# schema_mpb_1_1_Serial.net
KiCad netlist of a schematic drawn in EAGLE
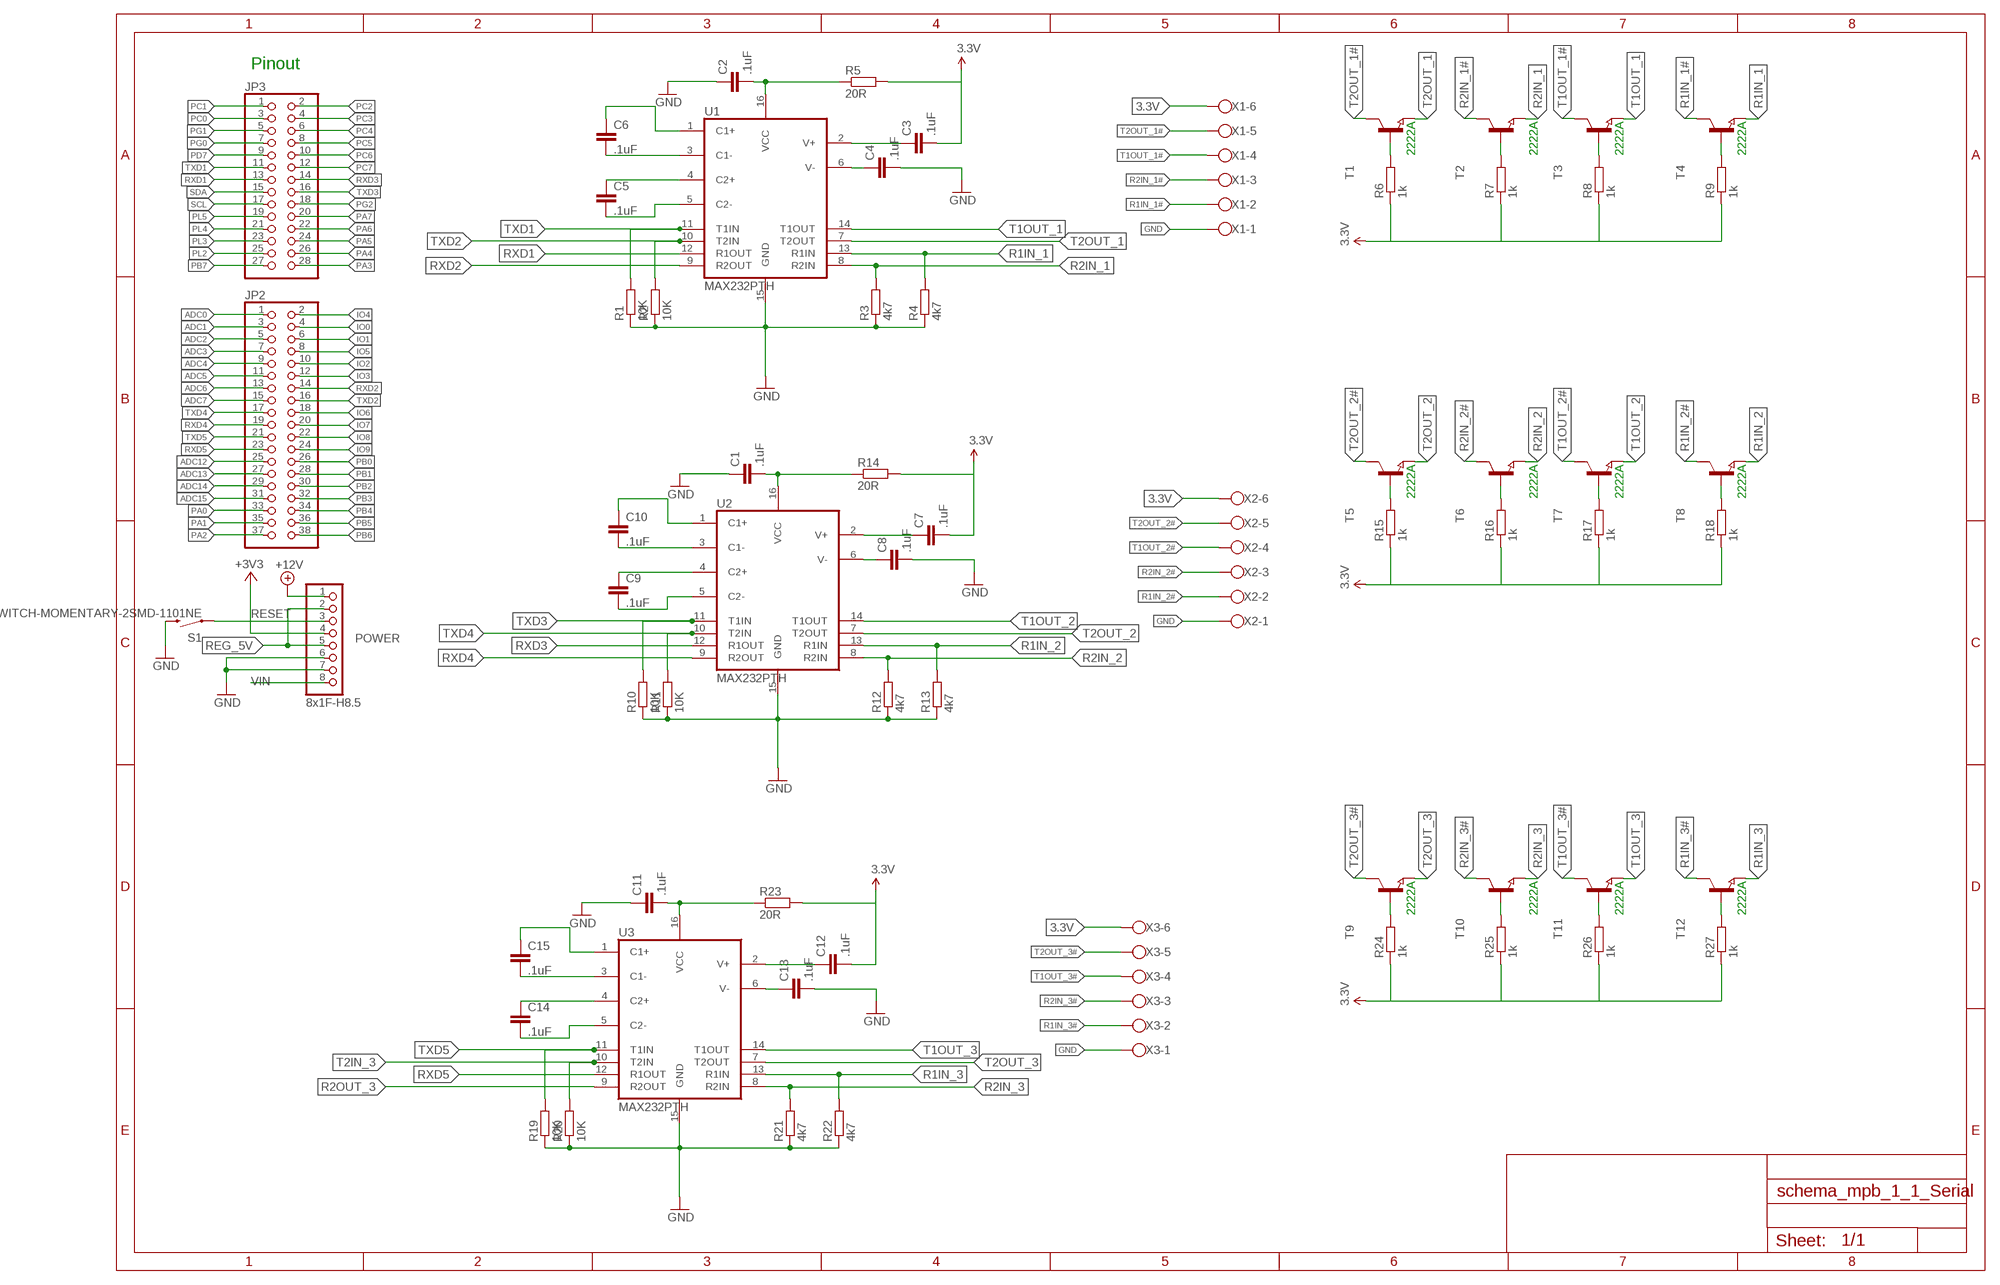
[diagram p0: schematic, sheet 1]

(export (version "E")
  (design (tool "Eeschema 10.0.6"))
  (components
    (comp (ref "C1")
      (value ".1uF")
      (footprint "eagle-import:C0805")
      (libsource (lib "eagle-import") (part "C-EUC0805"))
    )
    (comp (ref "C2")
      (value ".1uF")
      (footprint "eagle-import:C0805")
      (libsource (lib "eagle-import") (part "C-EUC0805"))
    )
    (comp (ref "C3")
      (value ".1uF")
      (footprint "eagle-import:C0805")
      (libsource (lib "eagle-import") (part "C-EUC0805"))
    )
    (comp (ref "C4")
      (value ".1uF")
      (footprint "eagle-import:C0805")
      (libsource (lib "eagle-import") (part "C-EUC0805"))
    )
    (comp (ref "C5")
      (value ".1uF")
      (footprint "eagle-import:C0805")
      (libsource (lib "eagle-import") (part "C-EUC0805"))
    )
    (comp (ref "C6")
      (value ".1uF")
      (footprint "eagle-import:C0805")
      (libsource (lib "eagle-import") (part "C-EUC0805"))
    )
    (comp (ref "C7")
      (value ".1uF")
      (footprint "eagle-import:C0805")
      (libsource (lib "eagle-import") (part "C-EUC0805"))
    )
    (comp (ref "C8")
      (value ".1uF")
      (footprint "eagle-import:C0805")
      (libsource (lib "eagle-import") (part "C-EUC0805"))
    )
    (comp (ref "C9")
      (value ".1uF")
      (footprint "eagle-import:C0805")
      (libsource (lib "eagle-import") (part "C-EUC0805"))
    )
    (comp (ref "C10")
      (value ".1uF")
      (footprint "eagle-import:C0805")
      (libsource (lib "eagle-import") (part "C-EUC0805"))
    )
    (comp (ref "C11")
      (value ".1uF")
      (footprint "eagle-import:C0805")
      (libsource (lib "eagle-import") (part "C-EUC0805"))
    )
    (comp (ref "C12")
      (value ".1uF")
      (footprint "eagle-import:C0805")
      (libsource (lib "eagle-import") (part "C-EUC0805"))
    )
    (comp (ref "C13")
      (value ".1uF")
      (footprint "eagle-import:C0805")
      (libsource (lib "eagle-import") (part "C-EUC0805"))
    )
    (comp (ref "C14")
      (value ".1uF")
      (footprint "eagle-import:C0805")
      (libsource (lib "eagle-import") (part "C-EUC0805"))
    )
    (comp (ref "C15")
      (value ".1uF")
      (footprint "eagle-import:C0805")
      (libsource (lib "eagle-import") (part "C-EUC0805"))
    )
    (comp (ref "JP2")
      (value "PINHD-2X19")
      (footprint "eagle-import:2X19")
      (libsource (lib "eagle-import") (part "PINHD-2X19"))
    )
    (comp (ref "JP3")
      (value "PINHD-2X14")
      (footprint "eagle-import:2X14")
      (libsource (lib "eagle-import") (part "PINHD-2X14"))
    )
    (comp (ref "POWER")
      (value "8x1F-H8.5")
      (footprint "eagle-import:1X08")
      (libsource (lib "eagle-import") (part "PINHD-1X8"))
    )
    (comp (ref "R1")
      (value "10K")
      (footprint "eagle-import:R0805")
      (libsource (lib "eagle-import") (part "R-EU_R0805"))
    )
    (comp (ref "R2")
      (value "10K")
      (footprint "eagle-import:R0805")
      (libsource (lib "eagle-import") (part "R-EU_R0805"))
    )
    (comp (ref "R3")
      (value "4k7")
      (footprint "eagle-import:R0805")
      (libsource (lib "eagle-import") (part "R-EU_R0805"))
    )
    (comp (ref "R4")
      (value "4k7")
      (footprint "eagle-import:R0805")
      (libsource (lib "eagle-import") (part "R-EU_R0805"))
    )
    (comp (ref "R5")
      (value "20R")
      (footprint "eagle-import:R0805")
      (libsource (lib "eagle-import") (part "R-EU_R0805"))
    )
    (comp (ref "R6")
      (value "1k")
      (footprint "eagle-import:R0805")
      (libsource (lib "eagle-import") (part "R-EU_R0805"))
    )
    (comp (ref "R7")
      (value "1k")
      (footprint "eagle-import:R0805")
      (libsource (lib "eagle-import") (part "R-EU_R0805"))
    )
    (comp (ref "R8")
      (value "1k")
      (footprint "eagle-import:R0805")
      (libsource (lib "eagle-import") (part "R-EU_R0805"))
    )
    (comp (ref "R9")
      (value "1k")
      (footprint "eagle-import:R0805")
      (libsource (lib "eagle-import") (part "R-EU_R0805"))
    )
    (comp (ref "R10")
      (value "10K")
      (footprint "eagle-import:R0805")
      (libsource (lib "eagle-import") (part "R-EU_R0805"))
    )
    (comp (ref "R11")
      (value "10K")
      (footprint "eagle-import:R0805")
      (libsource (lib "eagle-import") (part "R-EU_R0805"))
    )
    (comp (ref "R12")
      (value "4k7")
      (footprint "eagle-import:R0805")
      (libsource (lib "eagle-import") (part "R-EU_R0805"))
    )
    (comp (ref "R13")
      (value "4k7")
      (footprint "eagle-import:R0805")
      (libsource (lib "eagle-import") (part "R-EU_R0805"))
    )
    (comp (ref "R14")
      (value "20R")
      (footprint "eagle-import:R0805")
      (libsource (lib "eagle-import") (part "R-EU_R0805"))
    )
    (comp (ref "R15")
      (value "1k")
      (footprint "eagle-import:R0805")
      (libsource (lib "eagle-import") (part "R-EU_R0805"))
    )
    (comp (ref "R16")
      (value "1k")
      (footprint "eagle-import:R0805")
      (libsource (lib "eagle-import") (part "R-EU_R0805"))
    )
    (comp (ref "R17")
      (value "1k")
      (footprint "eagle-import:R0805")
      (libsource (lib "eagle-import") (part "R-EU_R0805"))
    )
    (comp (ref "R18")
      (value "1k")
      (footprint "eagle-import:R0805")
      (libsource (lib "eagle-import") (part "R-EU_R0805"))
    )
    (comp (ref "R19")
      (value "10K")
      (footprint "eagle-import:R0805")
      (libsource (lib "eagle-import") (part "R-EU_R0805"))
    )
    (comp (ref "R20")
      (value "10K")
      (footprint "eagle-import:R0805")
      (libsource (lib "eagle-import") (part "R-EU_R0805"))
    )
    (comp (ref "R21")
      (value "4k7")
      (footprint "eagle-import:R0805")
      (libsource (lib "eagle-import") (part "R-EU_R0805"))
    )
    (comp (ref "R22")
      (value "4k7")
      (footprint "eagle-import:R0805")
      (libsource (lib "eagle-import") (part "R-EU_R0805"))
    )
    (comp (ref "R23")
      (value "20R")
      (footprint "eagle-import:R0805")
      (libsource (lib "eagle-import") (part "R-EU_R0805"))
    )
    (comp (ref "R24")
      (value "1k")
      (footprint "eagle-import:R0805")
      (libsource (lib "eagle-import") (part "R-EU_R0805"))
    )
    (comp (ref "R25")
      (value "1k")
      (footprint "eagle-import:R0805")
      (libsource (lib "eagle-import") (part "R-EU_R0805"))
    )
    (comp (ref "R26")
      (value "1k")
      (footprint "eagle-import:R0805")
      (libsource (lib "eagle-import") (part "R-EU_R0805"))
    )
    (comp (ref "R27")
      (value "1k")
      (footprint "eagle-import:R0805")
      (libsource (lib "eagle-import") (part "R-EU_R0805"))
    )
    (comp (ref "S1")
      (value "SWITCH-MOMENTARY-2SMD-1101NE")
      (footprint "eagle-import:TACTILE-SWITCH-1101NE")
      (libsource (lib "eagle-import") (part "SWITCH-MOMENTARY-2SMD-1101NE"))
    )
    (comp (ref "T1")
      (value "NPN-TRANSISTOR_SOT23")
      (footprint "eagle-import:SOT23")
      (libsource (lib "eagle-import") (part "NPN-TRANSISTOR_SOT23"))
    )
    (comp (ref "T2")
      (value "NPN-TRANSISTOR_SOT23")
      (footprint "eagle-import:SOT23")
      (libsource (lib "eagle-import") (part "NPN-TRANSISTOR_SOT23"))
    )
    (comp (ref "T3")
      (value "NPN-TRANSISTOR_SOT23")
      (footprint "eagle-import:SOT23")
      (libsource (lib "eagle-import") (part "NPN-TRANSISTOR_SOT23"))
    )
    (comp (ref "T4")
      (value "NPN-TRANSISTOR_SOT23")
      (footprint "eagle-import:SOT23")
      (libsource (lib "eagle-import") (part "NPN-TRANSISTOR_SOT23"))
    )
    (comp (ref "T5")
      (value "NPN-TRANSISTOR_SOT23")
      (footprint "eagle-import:SOT23")
      (libsource (lib "eagle-import") (part "NPN-TRANSISTOR_SOT23"))
    )
    (comp (ref "T6")
      (value "NPN-TRANSISTOR_SOT23")
      (footprint "eagle-import:SOT23")
      (libsource (lib "eagle-import") (part "NPN-TRANSISTOR_SOT23"))
    )
    (comp (ref "T7")
      (value "NPN-TRANSISTOR_SOT23")
      (footprint "eagle-import:SOT23")
      (libsource (lib "eagle-import") (part "NPN-TRANSISTOR_SOT23"))
    )
    (comp (ref "T8")
      (value "NPN-TRANSISTOR_SOT23")
      (footprint "eagle-import:SOT23")
      (libsource (lib "eagle-import") (part "NPN-TRANSISTOR_SOT23"))
    )
    (comp (ref "T9")
      (value "NPN-TRANSISTOR_SOT23")
      (footprint "eagle-import:SOT23")
      (libsource (lib "eagle-import") (part "NPN-TRANSISTOR_SOT23"))
    )
    (comp (ref "T10")
      (value "NPN-TRANSISTOR_SOT23")
      (footprint "eagle-import:SOT23")
      (libsource (lib "eagle-import") (part "NPN-TRANSISTOR_SOT23"))
    )
    (comp (ref "T11")
      (value "NPN-TRANSISTOR_SOT23")
      (footprint "eagle-import:SOT23")
      (libsource (lib "eagle-import") (part "NPN-TRANSISTOR_SOT23"))
    )
    (comp (ref "T12")
      (value "NPN-TRANSISTOR_SOT23")
      (footprint "eagle-import:SOT23")
      (libsource (lib "eagle-import") (part "NPN-TRANSISTOR_SOT23"))
    )
    (comp (ref "U1")
      (value "MAX232PTH")
      (footprint "eagle-import:DIL16")
      (libsource (lib "eagle-import") (part "MAX232PTH"))
    )
    (comp (ref "U2")
      (value "MAX232PTH")
      (footprint "eagle-import:DIL16")
      (libsource (lib "eagle-import") (part "MAX232PTH"))
    )
    (comp (ref "U3")
      (value "MAX232PTH")
      (footprint "eagle-import:DIL16")
      (libsource (lib "eagle-import") (part "MAX232PTH"))
    )
    (comp (ref "X1")
      (value "W237-6")
      (footprint "eagle-import:W237-6")
      (libsource (lib "eagle-import") (part "W237-6"))
    )
    (comp (ref "X2")
      (value "W237-6")
      (footprint "eagle-import:W237-6")
      (libsource (lib "eagle-import") (part "W237-6"))
    )
    (comp (ref "X3")
      (value "W237-6")
      (footprint "eagle-import:W237-6")
      (libsource (lib "eagle-import") (part "W237-6"))
    )
  )
  (nets
    (net (code "1") (name "+12V") (class "Default")
      (node (ref "POWER") (pin "1") (pinfunction "1_1") (pintype "passive"))
    )
    (net (code "2") (name "/RESET") (class "Default")
      (node (ref "POWER") (pin "3") (pinfunction "3_3") (pintype "passive"))
      (node (ref "S1") (pin "1") (pinfunction "1_1") (pintype "passive"))
    )
    (net (code "3") (name "/VIN") (class "Default")
      (node (ref "POWER") (pin "8") (pinfunction "8_8") (pintype "passive"))
    )
    (net (code "4") (name "3.3V") (class "Default")
      (node (ref "C12") (pin "2") (pinfunction "2_2") (pintype "passive"))
      (node (ref "C3") (pin "2") (pinfunction "2_2") (pintype "passive"))
      (node (ref "C7") (pin "2") (pinfunction "2_2") (pintype "passive"))
      (node (ref "POWER") (pin "4") (pinfunction "4_4") (pintype "passive"))
      (node (ref "R14") (pin "2") (pinfunction "2_2") (pintype "passive"))
      (node (ref "R15") (pin "1") (pinfunction "1_1") (pintype "passive"))
      (node (ref "R16") (pin "1") (pinfunction "1_1") (pintype "passive"))
      (node (ref "R17") (pin "1") (pinfunction "1_1") (pintype "passive"))
      (node (ref "R18") (pin "1") (pinfunction "1_1") (pintype "passive"))
      (node (ref "R23") (pin "2") (pinfunction "2_2") (pintype "passive"))
      (node (ref "R24") (pin "1") (pinfunction "1_1") (pintype "passive"))
      (node (ref "R25") (pin "1") (pinfunction "1_1") (pintype "passive"))
      (node (ref "R26") (pin "1") (pinfunction "1_1") (pintype "passive"))
      (node (ref "R27") (pin "1") (pinfunction "1_1") (pintype "passive"))
      (node (ref "R5") (pin "2") (pinfunction "2_2") (pintype "passive"))
      (node (ref "R6") (pin "1") (pinfunction "1_1") (pintype "passive"))
      (node (ref "R7") (pin "1") (pinfunction "1_1") (pintype "passive"))
      (node (ref "R8") (pin "1") (pinfunction "1_1") (pintype "passive"))
      (node (ref "R9") (pin "1") (pinfunction "1_1") (pintype "passive"))
      (node (ref "X1") (pin "6") (pinfunction "KL_6") (pintype "passive"))
      (node (ref "X2") (pin "6") (pinfunction "KL_6") (pintype "passive"))
      (node (ref "X3") (pin "6") (pinfunction "KL_6") (pintype "passive"))
    )
    (net (code "5") (name "ADC0") (class "Default")
      (node (ref "JP2") (pin "1") (pinfunction "1_1") (pintype "passive"))
    )
    (net (code "6") (name "ADC1") (class "Default")
      (node (ref "JP2") (pin "3") (pinfunction "3_3") (pintype "passive"))
    )
    (net (code "7") (name "ADC2") (class "Default")
      (node (ref "JP2") (pin "5") (pinfunction "5_5") (pintype "passive"))
    )
    (net (code "8") (name "ADC3") (class "Default")
      (node (ref "JP2") (pin "7") (pinfunction "7_7") (pintype "passive"))
    )
    (net (code "9") (name "ADC4") (class "Default")
      (node (ref "JP2") (pin "9") (pinfunction "9_9") (pintype "passive"))
    )
    (net (code "10") (name "ADC5") (class "Default")
      (node (ref "JP2") (pin "11") (pinfunction "11_11") (pintype "passive"))
    )
    (net (code "11") (name "ADC6") (class "Default")
      (node (ref "JP2") (pin "13") (pinfunction "13_13") (pintype "passive"))
    )
    (net (code "12") (name "ADC7") (class "Default")
      (node (ref "JP2") (pin "15") (pinfunction "15_15") (pintype "passive"))
    )
    (net (code "13") (name "ADC12") (class "Default")
      (node (ref "JP2") (pin "25") (pinfunction "25_25") (pintype "passive"))
    )
    (net (code "14") (name "ADC13") (class "Default")
      (node (ref "JP2") (pin "27") (pinfunction "27_27") (pintype "passive"))
    )
    (net (code "15") (name "ADC14") (class "Default")
      (node (ref "JP2") (pin "29") (pinfunction "29_29") (pintype "passive"))
    )
    (net (code "16") (name "ADC15") (class "Default")
      (node (ref "JP2") (pin "31") (pinfunction "31_31") (pintype "passive"))
    )
    (net (code "17") (name "GND") (class "Default")
      (node (ref "C1") (pin "1") (pinfunction "1_1") (pintype "passive"))
      (node (ref "C11") (pin "1") (pinfunction "1_1") (pintype "passive"))
      (node (ref "C13") (pin "2") (pinfunction "2_2") (pintype "passive"))
      (node (ref "C2") (pin "1") (pinfunction "1_1") (pintype "passive"))
      (node (ref "C4") (pin "2") (pinfunction "2_2") (pintype "passive"))
      (node (ref "C8") (pin "2") (pinfunction "2_2") (pintype "passive"))
      (node (ref "POWER") (pin "6") (pinfunction "6_6") (pintype "passive"))
      (node (ref "POWER") (pin "7") (pinfunction "7_7") (pintype "passive"))
      (node (ref "R1") (pin "1") (pinfunction "1_1") (pintype "passive"))
      (node (ref "R10") (pin "1") (pinfunction "1_1") (pintype "passive"))
      (node (ref "R11") (pin "1") (pinfunction "1_1") (pintype "passive"))
      (node (ref "R12") (pin "1") (pinfunction "1_1") (pintype "passive"))
      (node (ref "R13") (pin "1") (pinfunction "1_1") (pintype "passive"))
      (node (ref "R19") (pin "1") (pinfunction "1_1") (pintype "passive"))
      (node (ref "R2") (pin "1") (pinfunction "1_1") (pintype "passive"))
      (node (ref "R20") (pin "1") (pinfunction "1_1") (pintype "passive"))
      (node (ref "R21") (pin "1") (pinfunction "1_1") (pintype "passive"))
      (node (ref "R22") (pin "1") (pinfunction "1_1") (pintype "passive"))
      (node (ref "R3") (pin "1") (pinfunction "1_1") (pintype "passive"))
      (node (ref "R4") (pin "1") (pinfunction "1_1") (pintype "passive"))
      (node (ref "S1") (pin "2") (pinfunction "2_2") (pintype "passive"))
      (node (ref "U1") (pin "15") (pinfunction "GND_15") (pintype "bidirectional"))
      (node (ref "U2") (pin "15") (pinfunction "GND_15") (pintype "bidirectional"))
      (node (ref "U3") (pin "15") (pinfunction "GND_15") (pintype "bidirectional"))
      (node (ref "X1") (pin "1") (pinfunction "KL_1") (pintype "passive"))
      (node (ref "X2") (pin "1") (pinfunction "KL_1") (pintype "passive"))
      (node (ref "X3") (pin "1") (pinfunction "KL_1") (pintype "passive"))
    )
    (net (code "18") (name "IO0") (class "Default")
      (node (ref "JP2") (pin "4") (pinfunction "4_4") (pintype "passive"))
    )
    (net (code "19") (name "IO1") (class "Default")
      (node (ref "JP2") (pin "6") (pinfunction "6_6") (pintype "passive"))
    )
    (net (code "20") (name "IO2") (class "Default")
      (node (ref "JP2") (pin "10") (pinfunction "10_10") (pintype "passive"))
    )
    (net (code "21") (name "IO3") (class "Default")
      (node (ref "JP2") (pin "12") (pinfunction "12_12") (pintype "passive"))
    )
    (net (code "22") (name "IO4") (class "Default")
      (node (ref "JP2") (pin "2") (pinfunction "2_2") (pintype "passive"))
    )
    (net (code "23") (name "IO5") (class "Default")
      (node (ref "JP2") (pin "8") (pinfunction "8_8") (pintype "passive"))
    )
    (net (code "24") (name "IO6") (class "Default")
      (node (ref "JP2") (pin "18") (pinfunction "18_18") (pintype "passive"))
    )
    (net (code "25") (name "IO7") (class "Default")
      (node (ref "JP2") (pin "20") (pinfunction "20_20") (pintype "passive"))
    )
    (net (code "26") (name "IO8") (class "Default")
      (node (ref "JP2") (pin "22") (pinfunction "22_22") (pintype "passive"))
    )
    (net (code "27") (name "IO9") (class "Default")
      (node (ref "JP2") (pin "24") (pinfunction "24_24") (pintype "passive"))
    )
    (net (code "28") (name "Net-(T1-B)") (class "Default")
      (node (ref "R6") (pin "2") (pinfunction "2_2") (pintype "passive"))
      (node (ref "T1") (pin "1") (pinfunction "B_1") (pintype "passive"))
    )
    (net (code "29") (name "Net-(T2-B)") (class "Default")
      (node (ref "R7") (pin "2") (pinfunction "2_2") (pintype "passive"))
      (node (ref "T2") (pin "1") (pinfunction "B_1") (pintype "passive"))
    )
    (net (code "30") (name "Net-(T3-B)") (class "Default")
      (node (ref "R8") (pin "2") (pinfunction "2_2") (pintype "passive"))
      (node (ref "T3") (pin "1") (pinfunction "B_1") (pintype "passive"))
    )
    (net (code "31") (name "Net-(T4-B)") (class "Default")
      (node (ref "R9") (pin "2") (pinfunction "2_2") (pintype "passive"))
      (node (ref "T4") (pin "1") (pinfunction "B_1") (pintype "passive"))
    )
    (net (code "32") (name "Net-(T5-B)") (class "Default")
      (node (ref "R15") (pin "2") (pinfunction "2_2") (pintype "passive"))
      (node (ref "T5") (pin "1") (pinfunction "B_1") (pintype "passive"))
    )
    (net (code "33") (name "Net-(T6-B)") (class "Default")
      (node (ref "R16") (pin "2") (pinfunction "2_2") (pintype "passive"))
      (node (ref "T6") (pin "1") (pinfunction "B_1") (pintype "passive"))
    )
    (net (code "34") (name "Net-(T7-B)") (class "Default")
      (node (ref "R17") (pin "2") (pinfunction "2_2") (pintype "passive"))
      (node (ref "T7") (pin "1") (pinfunction "B_1") (pintype "passive"))
    )
    (net (code "35") (name "Net-(T8-B)") (class "Default")
      (node (ref "R18") (pin "2") (pinfunction "2_2") (pintype "passive"))
      (node (ref "T8") (pin "1") (pinfunction "B_1") (pintype "passive"))
    )
    (net (code "36") (name "Net-(T9-B)") (class "Default")
      (node (ref "R24") (pin "2") (pinfunction "2_2") (pintype "passive"))
      (node (ref "T9") (pin "1") (pinfunction "B_1") (pintype "passive"))
    )
    (net (code "37") (name "Net-(T10-B)") (class "Default")
      (node (ref "R25") (pin "2") (pinfunction "2_2") (pintype "passive"))
      (node (ref "T10") (pin "1") (pinfunction "B_1") (pintype "passive"))
    )
    (net (code "38") (name "Net-(T11-B)") (class "Default")
      (node (ref "R26") (pin "2") (pinfunction "2_2") (pintype "passive"))
      (node (ref "T11") (pin "1") (pinfunction "B_1") (pintype "passive"))
    )
    (net (code "39") (name "Net-(T12-B)") (class "Default")
      (node (ref "R27") (pin "2") (pinfunction "2_2") (pintype "passive"))
      (node (ref "T12") (pin "1") (pinfunction "B_1") (pintype "passive"))
    )
    (net (code "40") (name "Net-(U1-C1+)") (class "Default")
      (node (ref "C6") (pin "1") (pinfunction "1_1") (pintype "passive"))
      (node (ref "U1") (pin "1") (pinfunction "C1+_1") (pintype "bidirectional"))
    )
    (net (code "41") (name "Net-(U1-C1-)") (class "Default")
      (node (ref "C6") (pin "2") (pinfunction "2_2") (pintype "passive"))
      (node (ref "U1") (pin "3") (pinfunction "C1-_3") (pintype "bidirectional"))
    )
    (net (code "42") (name "Net-(U1-C2+)") (class "Default")
      (node (ref "C5") (pin "1") (pinfunction "1_1") (pintype "passive"))
      (node (ref "U1") (pin "4") (pinfunction "C2+_4") (pintype "bidirectional"))
    )
    (net (code "43") (name "Net-(U1-C2-)") (class "Default")
      (node (ref "C5") (pin "2") (pinfunction "2_2") (pintype "passive"))
      (node (ref "U1") (pin "5") (pinfunction "C2-_5") (pintype "bidirectional"))
    )
    (net (code "44") (name "Net-(U1-V+)") (class "Default")
      (node (ref "C3") (pin "1") (pinfunction "1_1") (pintype "passive"))
      (node (ref "U1") (pin "2") (pinfunction "V+_2") (pintype "bidirectional"))
    )
    (net (code "45") (name "Net-(U1-V-)") (class "Default")
      (node (ref "C4") (pin "1") (pinfunction "1_1") (pintype "passive"))
      (node (ref "U1") (pin "6") (pinfunction "V-_6") (pintype "bidirectional"))
    )
    (net (code "46") (name "Net-(U1-VCC)") (class "Default")
      (node (ref "C2") (pin "2") (pinfunction "2_2") (pintype "passive"))
      (node (ref "R5") (pin "1") (pinfunction "1_1") (pintype "passive"))
      (node (ref "U1") (pin "16") (pinfunction "VCC_16") (pintype "bidirectional"))
    )
    (net (code "47") (name "Net-(U2-C1+)") (class "Default")
      (node (ref "C10") (pin "1") (pinfunction "1_1") (pintype "passive"))
      (node (ref "U2") (pin "1") (pinfunction "C1+_1") (pintype "bidirectional"))
    )
    (net (code "48") (name "Net-(U2-C1-)") (class "Default")
      (node (ref "C10") (pin "2") (pinfunction "2_2") (pintype "passive"))
      (node (ref "U2") (pin "3") (pinfunction "C1-_3") (pintype "bidirectional"))
    )
    (net (code "49") (name "Net-(U2-C2+)") (class "Default")
      (node (ref "C9") (pin "1") (pinfunction "1_1") (pintype "passive"))
      (node (ref "U2") (pin "4") (pinfunction "C2+_4") (pintype "bidirectional"))
    )
    (net (code "50") (name "Net-(U2-C2-)") (class "Default")
      (node (ref "C9") (pin "2") (pinfunction "2_2") (pintype "passive"))
      (node (ref "U2") (pin "5") (pinfunction "C2-_5") (pintype "bidirectional"))
    )
    (net (code "51") (name "Net-(U2-V+)") (class "Default")
      (node (ref "C7") (pin "1") (pinfunction "1_1") (pintype "passive"))
      (node (ref "U2") (pin "2") (pinfunction "V+_2") (pintype "bidirectional"))
    )
    (net (code "52") (name "Net-(U2-V-)") (class "Default")
      (node (ref "C8") (pin "1") (pinfunction "1_1") (pintype "passive"))
      (node (ref "U2") (pin "6") (pinfunction "V-_6") (pintype "bidirectional"))
    )
    (net (code "53") (name "Net-(U2-VCC)") (class "Default")
      (node (ref "C1") (pin "2") (pinfunction "2_2") (pintype "passive"))
      (node (ref "R14") (pin "1") (pinfunction "1_1") (pintype "passive"))
      (node (ref "U2") (pin "16") (pinfunction "VCC_16") (pintype "bidirectional"))
    )
    (net (code "54") (name "Net-(U3-C1+)") (class "Default")
      (node (ref "C15") (pin "1") (pinfunction "1_1") (pintype "passive"))
      (node (ref "U3") (pin "1") (pinfunction "C1+_1") (pintype "bidirectional"))
    )
    (net (code "55") (name "Net-(U3-C1-)") (class "Default")
      (node (ref "C15") (pin "2") (pinfunction "2_2") (pintype "passive"))
      (node (ref "U3") (pin "3") (pinfunction "C1-_3") (pintype "bidirectional"))
    )
    (net (code "56") (name "Net-(U3-C2+)") (class "Default")
      (node (ref "C14") (pin "1") (pinfunction "1_1") (pintype "passive"))
      (node (ref "U3") (pin "4") (pinfunction "C2+_4") (pintype "bidirectional"))
    )
    (net (code "57") (name "Net-(U3-C2-)") (class "Default")
      (node (ref "C14") (pin "2") (pinfunction "2_2") (pintype "passive"))
      (node (ref "U3") (pin "5") (pinfunction "C2-_5") (pintype "bidirectional"))
    )
    (net (code "58") (name "Net-(U3-V+)") (class "Default")
      (node (ref "C12") (pin "1") (pinfunction "1_1") (pintype "passive"))
      (node (ref "U3") (pin "2") (pinfunction "V+_2") (pintype "bidirectional"))
    )
    (net (code "59") (name "Net-(U3-V-)") (class "Default")
      (node (ref "C13") (pin "1") (pinfunction "1_1") (pintype "passive"))
      (node (ref "U3") (pin "6") (pinfunction "V-_6") (pintype "bidirectional"))
    )
    (net (code "60") (name "Net-(U3-VCC)") (class "Default")
      (node (ref "C11") (pin "2") (pinfunction "2_2") (pintype "passive"))
      (node (ref "R23") (pin "1") (pinfunction "1_1") (pintype "passive"))
      (node (ref "U3") (pin "16") (pinfunction "VCC_16") (pintype "bidirectional"))
    )
    (net (code "61") (name "PA0") (class "Default")
      (node (ref "JP2") (pin "33") (pinfunction "33_33") (pintype "passive"))
    )
    (net (code "62") (name "PA1") (class "Default")
      (node (ref "JP2") (pin "35") (pinfunction "35_35") (pintype "passive"))
    )
    (net (code "63") (name "PA2") (class "Default")
      (node (ref "JP2") (pin "37") (pinfunction "37_37") (pintype "passive"))
    )
    (net (code "64") (name "PA3") (class "Default")
      (node (ref "JP3") (pin "28") (pinfunction "28_28") (pintype "passive"))
    )
    (net (code "65") (name "PA4") (class "Default")
      (node (ref "JP3") (pin "26") (pinfunction "26_26") (pintype "passive"))
    )
    (net (code "66") (name "PA5") (class "Default")
      (node (ref "JP3") (pin "24") (pinfunction "24_24") (pintype "passive"))
    )
    (net (code "67") (name "PA6") (class "Default")
      (node (ref "JP3") (pin "22") (pinfunction "22_22") (pintype "passive"))
    )
    (net (code "68") (name "PA7") (class "Default")
      (node (ref "JP3") (pin "20") (pinfunction "20_20") (pintype "passive"))
    )
    (net (code "69") (name "PB0") (class "Default")
      (node (ref "JP2") (pin "26") (pinfunction "26_26") (pintype "passive"))
    )
    (net (code "70") (name "PB1") (class "Default")
      (node (ref "JP2") (pin "28") (pinfunction "28_28") (pintype "passive"))
    )
    (net (code "71") (name "PB2") (class "Default")
      (node (ref "JP2") (pin "30") (pinfunction "30_30") (pintype "passive"))
    )
    (net (code "72") (name "PB3") (class "Default")
      (node (ref "JP2") (pin "32") (pinfunction "32_32") (pintype "passive"))
    )
    (net (code "73") (name "PB4") (class "Default")
      (node (ref "JP2") (pin "34") (pinfunction "34_34") (pintype "passive"))
    )
    (net (code "74") (name "PB5") (class "Default")
      (node (ref "JP2") (pin "36") (pinfunction "36_36") (pintype "passive"))
    )
    (net (code "75") (name "PB6") (class "Default")
      (node (ref "JP2") (pin "38") (pinfunction "38_38") (pintype "passive"))
    )
    (net (code "76") (name "PB7") (class "Default")
      (node (ref "JP3") (pin "27") (pinfunction "27_27") (pintype "passive"))
    )
    (net (code "77") (name "PC0") (class "Default")
      (node (ref "JP3") (pin "3") (pinfunction "3_3") (pintype "passive"))
    )
    (net (code "78") (name "PC1") (class "Default")
      (node (ref "JP3") (pin "1") (pinfunction "1_1") (pintype "passive"))
    )
    (net (code "79") (name "PC2") (class "Default")
      (node (ref "JP3") (pin "2") (pinfunction "2_2") (pintype "passive"))
    )
    (net (code "80") (name "PC3") (class "Default")
      (node (ref "JP3") (pin "4") (pinfunction "4_4") (pintype "passive"))
    )
    (net (code "81") (name "PC4") (class "Default")
      (node (ref "JP3") (pin "6") (pinfunction "6_6") (pintype "passive"))
    )
    (net (code "82") (name "PC5") (class "Default")
      (node (ref "JP3") (pin "8") (pinfunction "8_8") (pintype "passive"))
    )
    (net (code "83") (name "PC6") (class "Default")
      (node (ref "JP3") (pin "10") (pinfunction "10_10") (pintype "passive"))
    )
    (net (code "84") (name "PC7") (class "Default")
      (node (ref "JP3") (pin "12") (pinfunction "12_12") (pintype "passive"))
    )
    (net (code "85") (name "PD7") (class "Default")
      (node (ref "JP3") (pin "9") (pinfunction "9_9") (pintype "passive"))
    )
    (net (code "86") (name "PG0") (class "Default")
      (node (ref "JP3") (pin "7") (pinfunction "7_7") (pintype "passive"))
    )
    (net (code "87") (name "PG1") (class "Default")
      (node (ref "JP3") (pin "5") (pinfunction "5_5") (pintype "passive"))
    )
    (net (code "88") (name "PG2") (class "Default")
      (node (ref "JP3") (pin "18") (pinfunction "18_18") (pintype "passive"))
    )
    (net (code "89") (name "PL2") (class "Default")
      (node (ref "JP3") (pin "25") (pinfunction "25_25") (pintype "passive"))
    )
    (net (code "90") (name "PL3") (class "Default")
      (node (ref "JP3") (pin "23") (pinfunction "23_23") (pintype "passive"))
    )
    (net (code "91") (name "PL4") (class "Default")
      (node (ref "JP3") (pin "21") (pinfunction "21_21") (pintype "passive"))
    )
    (net (code "92") (name "PL5") (class "Default")
      (node (ref "JP3") (pin "19") (pinfunction "19_19") (pintype "passive"))
    )
    (net (code "93") (name "R1IN_1") (class "Default")
      (node (ref "R4") (pin "2") (pinfunction "2_2") (pintype "passive"))
      (node (ref "T4") (pin "2") (pinfunction "E_2") (pintype "passive"))
      (node (ref "U1") (pin "13") (pinfunction "R1IN_13") (pintype "input"))
    )
    (net (code "94") (name "R1IN_1#") (class "Default")
      (node (ref "T4") (pin "3") (pinfunction "C_3") (pintype "passive"))
      (node (ref "X1") (pin "2") (pinfunction "KL_2") (pintype "passive"))
    )
    (net (code "95") (name "R1IN_2") (class "Default")
      (node (ref "R13") (pin "2") (pinfunction "2_2") (pintype "passive"))
      (node (ref "T8") (pin "2") (pinfunction "E_2") (pintype "passive"))
      (node (ref "U2") (pin "13") (pinfunction "R1IN_13") (pintype "input"))
    )
    (net (code "96") (name "R1IN_2#") (class "Default")
      (node (ref "T8") (pin "3") (pinfunction "C_3") (pintype "passive"))
      (node (ref "X2") (pin "2") (pinfunction "KL_2") (pintype "passive"))
    )
    (net (code "97") (name "R1IN_3") (class "Default")
      (node (ref "R22") (pin "2") (pinfunction "2_2") (pintype "passive"))
      (node (ref "T12") (pin "2") (pinfunction "E_2") (pintype "passive"))
      (node (ref "U3") (pin "13") (pinfunction "R1IN_13") (pintype "input"))
    )
    (net (code "98") (name "R1IN_3#") (class "Default")
      (node (ref "T12") (pin "3") (pinfunction "C_3") (pintype "passive"))
      (node (ref "X3") (pin "2") (pinfunction "KL_2") (pintype "passive"))
    )
    (net (code "99") (name "R2IN_1") (class "Default")
      (node (ref "R3") (pin "2") (pinfunction "2_2") (pintype "passive"))
      (node (ref "T2") (pin "2") (pinfunction "E_2") (pintype "passive"))
      (node (ref "U1") (pin "8") (pinfunction "R2IN_8") (pintype "input"))
    )
    (net (code "100") (name "R2IN_1#") (class "Default")
      (node (ref "T2") (pin "3") (pinfunction "C_3") (pintype "passive"))
      (node (ref "X1") (pin "3") (pinfunction "KL_3") (pintype "passive"))
    )
    (net (code "101") (name "R2IN_2") (class "Default")
      (node (ref "R12") (pin "2") (pinfunction "2_2") (pintype "passive"))
      (node (ref "T6") (pin "2") (pinfunction "E_2") (pintype "passive"))
      (node (ref "U2") (pin "8") (pinfunction "R2IN_8") (pintype "input"))
    )
    (net (code "102") (name "R2IN_2#") (class "Default")
      (node (ref "T6") (pin "3") (pinfunction "C_3") (pintype "passive"))
      (node (ref "X2") (pin "3") (pinfunction "KL_3") (pintype "passive"))
    )
    (net (code "103") (name "R2IN_3") (class "Default")
      (node (ref "R21") (pin "2") (pinfunction "2_2") (pintype "passive"))
      (node (ref "T10") (pin "2") (pinfunction "E_2") (pintype "passive"))
      (node (ref "U3") (pin "8") (pinfunction "R2IN_8") (pintype "input"))
    )
    (net (code "104") (name "R2IN_3#") (class "Default")
      (node (ref "T10") (pin "3") (pinfunction "C_3") (pintype "passive"))
      (node (ref "X3") (pin "3") (pinfunction "KL_3") (pintype "passive"))
    )
    (net (code "105") (name "R2OUT_3") (class "Default")
      (node (ref "U3") (pin "9") (pinfunction "R2OUT_9") (pintype "output"))
    )
    (net (code "106") (name "REG_5V") (class "Default")
      (node (ref "POWER") (pin "2") (pinfunction "2_2") (pintype "passive"))
      (node (ref "POWER") (pin "5") (pinfunction "5_5") (pintype "passive"))
    )
    (net (code "107") (name "RXD1") (class "Default")
      (node (ref "JP3") (pin "13") (pinfunction "13_13") (pintype "passive"))
      (node (ref "U1") (pin "12") (pinfunction "R1OUT_12") (pintype "output"))
    )
    (net (code "108") (name "RXD2") (class "Default")
      (node (ref "JP2") (pin "14") (pinfunction "14_14") (pintype "passive"))
      (node (ref "U1") (pin "9") (pinfunction "R2OUT_9") (pintype "output"))
    )
    (net (code "109") (name "RXD3") (class "Default")
      (node (ref "JP3") (pin "14") (pinfunction "14_14") (pintype "passive"))
      (node (ref "U2") (pin "12") (pinfunction "R1OUT_12") (pintype "output"))
    )
    (net (code "110") (name "RXD4") (class "Default")
      (node (ref "JP2") (pin "19") (pinfunction "19_19") (pintype "passive"))
      (node (ref "U2") (pin "9") (pinfunction "R2OUT_9") (pintype "output"))
    )
    (net (code "111") (name "RXD5") (class "Default")
      (node (ref "JP2") (pin "23") (pinfunction "23_23") (pintype "passive"))
      (node (ref "U3") (pin "12") (pinfunction "R1OUT_12") (pintype "output"))
    )
    (net (code "112") (name "SCL") (class "Default")
      (node (ref "JP3") (pin "17") (pinfunction "17_17") (pintype "passive"))
    )
    (net (code "113") (name "SDA") (class "Default")
      (node (ref "JP3") (pin "15") (pinfunction "15_15") (pintype "passive"))
    )
    (net (code "114") (name "T1OUT_1") (class "Default")
      (node (ref "T3") (pin "2") (pinfunction "E_2") (pintype "passive"))
      (node (ref "U1") (pin "14") (pinfunction "T1OUT_14") (pintype "output"))
    )
    (net (code "115") (name "T1OUT_1#") (class "Default")
      (node (ref "T3") (pin "3") (pinfunction "C_3") (pintype "passive"))
      (node (ref "X1") (pin "4") (pinfunction "KL_4") (pintype "passive"))
    )
    (net (code "116") (name "T1OUT_2") (class "Default")
      (node (ref "T7") (pin "2") (pinfunction "E_2") (pintype "passive"))
      (node (ref "U2") (pin "14") (pinfunction "T1OUT_14") (pintype "output"))
    )
    (net (code "117") (name "T1OUT_2#") (class "Default")
      (node (ref "T7") (pin "3") (pinfunction "C_3") (pintype "passive"))
      (node (ref "X2") (pin "4") (pinfunction "KL_4") (pintype "passive"))
    )
    (net (code "118") (name "T1OUT_3") (class "Default")
      (node (ref "T11") (pin "2") (pinfunction "E_2") (pintype "passive"))
      (node (ref "U3") (pin "14") (pinfunction "T1OUT_14") (pintype "output"))
    )
    (net (code "119") (name "T1OUT_3#") (class "Default")
      (node (ref "T11") (pin "3") (pinfunction "C_3") (pintype "passive"))
      (node (ref "X3") (pin "4") (pinfunction "KL_4") (pintype "passive"))
    )
    (net (code "120") (name "T2IN_3") (class "Default")
      (node (ref "R20") (pin "2") (pinfunction "2_2") (pintype "passive"))
      (node (ref "U3") (pin "10") (pinfunction "T2IN_10") (pintype "input"))
    )
    (net (code "121") (name "T2OUT_1") (class "Default")
      (node (ref "T1") (pin "2") (pinfunction "E_2") (pintype "passive"))
      (node (ref "U1") (pin "7") (pinfunction "T2OUT_7") (pintype "output"))
    )
    (net (code "122") (name "T2OUT_1#") (class "Default")
      (node (ref "T1") (pin "3") (pinfunction "C_3") (pintype "passive"))
      (node (ref "X1") (pin "5") (pinfunction "KL_5") (pintype "passive"))
    )
    (net (code "123") (name "T2OUT_2") (class "Default")
      (node (ref "T5") (pin "2") (pinfunction "E_2") (pintype "passive"))
      (node (ref "U2") (pin "7") (pinfunction "T2OUT_7") (pintype "output"))
    )
    (net (code "124") (name "T2OUT_2#") (class "Default")
      (node (ref "T5") (pin "3") (pinfunction "C_3") (pintype "passive"))
      (node (ref "X2") (pin "5") (pinfunction "KL_5") (pintype "passive"))
    )
    (net (code "125") (name "T2OUT_3") (class "Default")
      (node (ref "T9") (pin "2") (pinfunction "E_2") (pintype "passive"))
      (node (ref "U3") (pin "7") (pinfunction "T2OUT_7") (pintype "output"))
    )
    (net (code "126") (name "T2OUT_3#") (class "Default")
      (node (ref "T9") (pin "3") (pinfunction "C_3") (pintype "passive"))
      (node (ref "X3") (pin "5") (pinfunction "KL_5") (pintype "passive"))
    )
    (net (code "127") (name "TXD1") (class "Default")
      (node (ref "JP3") (pin "11") (pinfunction "11_11") (pintype "passive"))
      (node (ref "R1") (pin "2") (pinfunction "2_2") (pintype "passive"))
      (node (ref "U1") (pin "11") (pinfunction "T1IN_11") (pintype "input"))
    )
    (net (code "128") (name "TXD2") (class "Default")
      (node (ref "JP2") (pin "16") (pinfunction "16_16") (pintype "passive"))
      (node (ref "R2") (pin "2") (pinfunction "2_2") (pintype "passive"))
      (node (ref "U1") (pin "10") (pinfunction "T2IN_10") (pintype "input"))
    )
    (net (code "129") (name "TXD3") (class "Default")
      (node (ref "JP3") (pin "16") (pinfunction "16_16") (pintype "passive"))
      (node (ref "R10") (pin "2") (pinfunction "2_2") (pintype "passive"))
      (node (ref "U2") (pin "11") (pinfunction "T1IN_11") (pintype "input"))
    )
    (net (code "130") (name "TXD4") (class "Default")
      (node (ref "JP2") (pin "17") (pinfunction "17_17") (pintype "passive"))
      (node (ref "R11") (pin "2") (pinfunction "2_2") (pintype "passive"))
      (node (ref "U2") (pin "10") (pinfunction "T2IN_10") (pintype "input"))
    )
    (net (code "131") (name "TXD5") (class "Default")
      (node (ref "JP2") (pin "21") (pinfunction "21_21") (pintype "passive"))
      (node (ref "R19") (pin "2") (pinfunction "2_2") (pintype "passive"))
      (node (ref "U3") (pin "11") (pinfunction "T1IN_11") (pintype "input"))
    )
  )
)
